# lilypad_V2.net
KiCad netlist of a schematic drawn in EAGLE
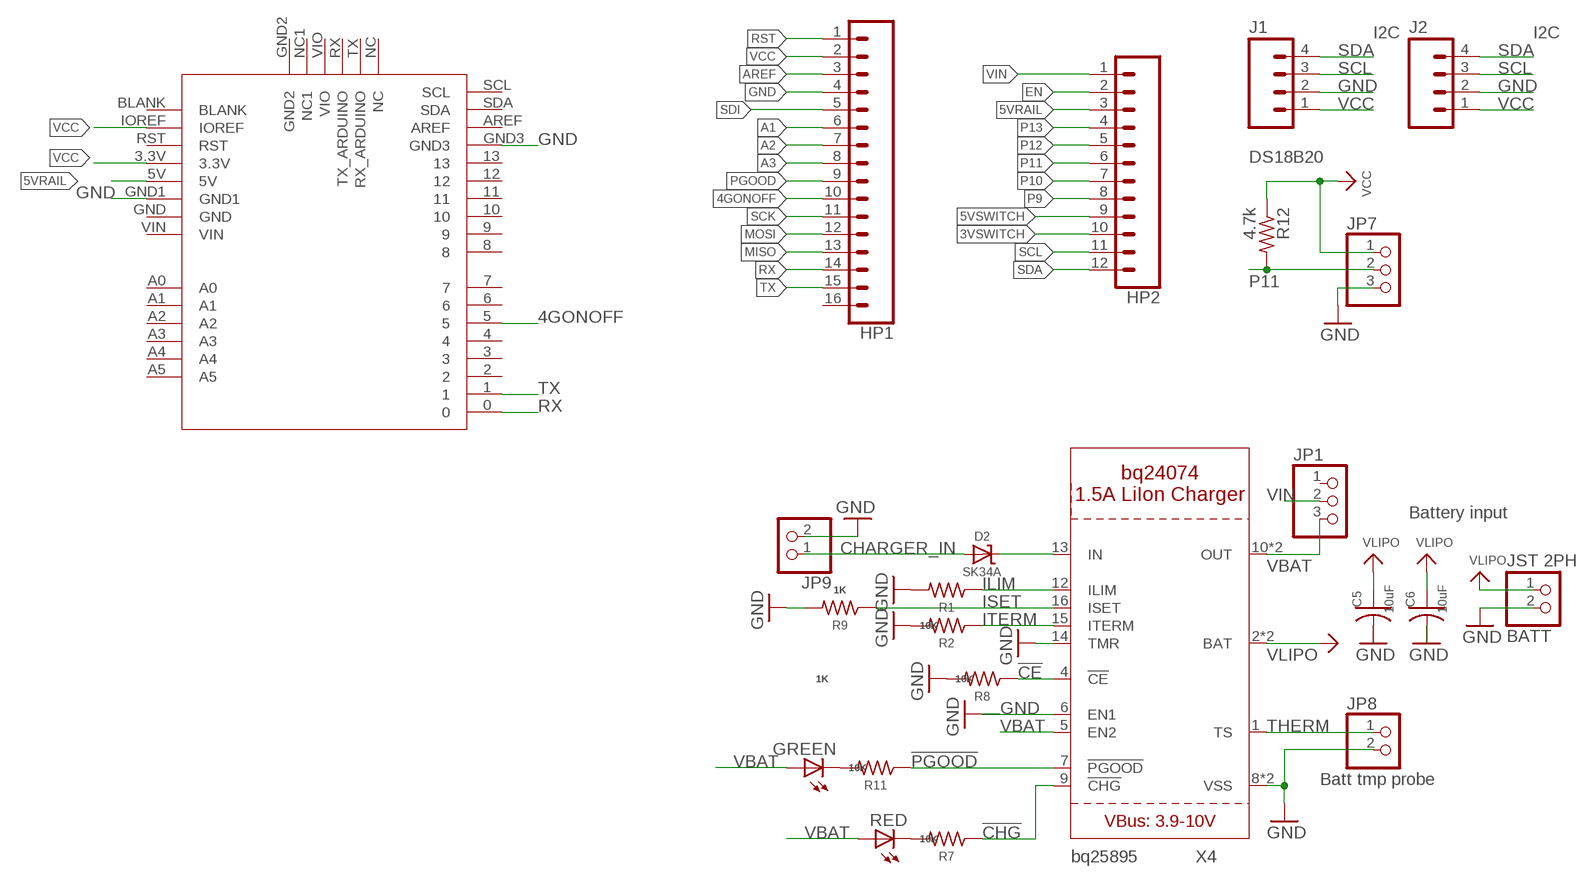
[diagram p0: schematic, sheet 1]

(export (version "E")
  (design (tool "Eeschema 10.0.6"))
  (components
    (comp (ref "BATT")
      (value "JST 2PH")
      (footprint "eagle-import:JST-PH-2-SMT-RA")
      (libsource (lib "eagle-import") (part "JST_2PIN-SMT-RA"))
    )
    (comp (ref "C5")
      (value "10uF")
      (footprint "eagle-import:C0805K")
      (libsource (lib "eagle-import") (part "C-USC0805K"))
    )
    (comp (ref "C6")
      (value "10uF")
      (footprint "eagle-import:C0805K")
      (libsource (lib "eagle-import") (part "C-USC0805K"))
    )
    (comp (ref "D2")
      (value "SK34A")
      (footprint "eagle-import:SMADIODE")
      (libsource (lib "eagle-import") (part "DIODE-SCHOTTKYSMA"))
    )
    (comp (ref "GREEN")
      (value "LEDSMT1206")
      (footprint "eagle-import:1206")
      (libsource (lib "eagle-import") (part "LEDSMT1206"))
    )
    (comp (ref "HP1")
      (value "CONN_16")
      (footprint "eagle-import:1X16")
      (libsource (lib "eagle-import") (part "CONN_16"))
    )
    (comp (ref "HP2")
      (value "CONN_12")
      (footprint "eagle-import:1X12")
      (libsource (lib "eagle-import") (part "CONN_12"))
    )
    (comp (ref "J1")
      (value "M04PTH")
      (footprint "eagle-import:1X04")
      (libsource (lib "eagle-import") (part "M04PTH"))
    )
    (comp (ref "J2")
      (value "M04PTH")
      (footprint "eagle-import:1X04")
      (libsource (lib "eagle-import") (part "M04PTH"))
    )
    (comp (ref "JP1")
      (value "PINHD-1X3")
      (footprint "eagle-import:1X03")
      (libsource (lib "eagle-import") (part "PINHD-1X3"))
    )
    (comp (ref "JP7")
      (value "PINHD-1X3")
      (footprint "eagle-import:1X03")
      (libsource (lib "eagle-import") (part "PINHD-1X3"))
    )
    (comp (ref "JP8")
      (value "PINHD-1X2")
      (footprint "eagle-import:1X02")
      (libsource (lib "eagle-import") (part "PINHD-1X2"))
    )
    (comp (ref "JP9")
      (value "PINHD-1X2")
      (footprint "eagle-import:1X02")
      (libsource (lib "eagle-import") (part "PINHD-1X2"))
    )
    (comp (ref "R1")
      (value "1K")
      (footprint "eagle-import:M0805")
      (libsource (lib "eagle-import") (part "R-US_M0805"))
    )
    (comp (ref "R2")
      (value "10K")
      (footprint "eagle-import:M0805")
      (libsource (lib "eagle-import") (part "R-US_M0805"))
    )
    (comp (ref "R7")
      (value "10K")
      (footprint "eagle-import:M0805")
      (libsource (lib "eagle-import") (part "R-US_M0805"))
    )
    (comp (ref "R8")
      (value "10K")
      (footprint "eagle-import:M0805")
      (libsource (lib "eagle-import") (part "R-US_M0805"))
    )
    (comp (ref "R9")
      (value "1K")
      (footprint "eagle-import:M0805")
      (libsource (lib "eagle-import") (part "R-US_M0805"))
    )
    (comp (ref "R11")
      (value "10K")
      (footprint "eagle-import:M0805")
      (libsource (lib "eagle-import") (part "R-US_M0805"))
    )
    (comp (ref "R12")
      (value "4.7k")
      (footprint "eagle-import:0805-THM")
      (libsource (lib "eagle-import") (part "FLIPFLOP-RES"))
    )
    (comp (ref "RED")
      (value "LEDSMT1206")
      (footprint "eagle-import:1206")
      (libsource (lib "eagle-import") (part "LEDSMT1206"))
    )
    (comp (ref "U$2")
      (value "LTE_BOARD")
      (footprint "eagle-import:LTE_BOARD_FOOTPRINT")
      (libsource (lib "eagle-import") (part "LTE_BOARD"))
    )
    (comp (ref "X4")
      (value "BQ24074")
      (footprint "eagle-import:QFN16_3MM")
      (libsource (lib "eagle-import") (part "BQ24074"))
    )
  )
  (nets
    (net (code "1") (name "/CHARGER_IN") (class "Default")
      (node (ref "D2") (pin "A") (pinfunction "A_A") (pintype "passive"))
      (node (ref "JP9") (pin "1") (pinfunction "1_1") (pintype "passive"))
    )
    (net (code "2") (name "/ILIM") (class "Default")
      (node (ref "R1") (pin "1") (pinfunction "1_1") (pintype "passive"))
      (node (ref "X4") (pin "12") (pinfunction "ILIM_12") (pintype "input"))
    )
    (net (code "3") (name "/ISET") (class "Default")
      (node (ref "R9") (pin "1") (pinfunction "1_1") (pintype "passive"))
      (node (ref "X4") (pin "16") (pinfunction "ISET_16") (pintype "input"))
    )
    (net (code "4") (name "/ITERM") (class "Default")
      (node (ref "R2") (pin "1") (pinfunction "1_1") (pintype "passive"))
      (node (ref "X4") (pin "15") (pinfunction "ITERM_15") (pintype "input"))
    )
    (net (code "5") (name "/THERM") (class "Default")
      (node (ref "JP8") (pin "1") (pinfunction "1_1") (pintype "passive"))
      (node (ref "X4") (pin "1") (pinfunction "TS_1") (pintype "input"))
    )
    (net (code "6") (name "/VBAT") (class "Default")
      (node (ref "GREEN") (pin "A") (pinfunction "A_A") (pintype "passive"))
      (node (ref "JP1") (pin "3") (pinfunction "3_3") (pintype "passive"))
      (node (ref "RED") (pin "A") (pinfunction "A_A") (pintype "passive"))
      (node (ref "X4") (pin "10") (pinfunction "OUT_10") (pintype "output"))
      (node (ref "X4") (pin "11") (pinfunction "OUT_11") (pintype "output"))
      (node (ref "X4") (pin "5") (pinfunction "EN2_5") (pintype "input"))
    )
    (net (code "7") (name "/~{CE}") (class "Default")
      (node (ref "R8") (pin "1") (pinfunction "1_1") (pintype "passive"))
      (node (ref "X4") (pin "4") (pinfunction "~{CE}_4") (pintype "input"))
    )
    (net (code "8") (name "/~{CHG}") (class "Default")
      (node (ref "R7") (pin "1") (pinfunction "1_1") (pintype "passive"))
      (node (ref "X4") (pin "9") (pinfunction "~{CHG}_9") (pintype "output"))
    )
    (net (code "9") (name "/~{PGOOD}") (class "Default")
      (node (ref "R11") (pin "1") (pinfunction "1_1") (pintype "passive"))
      (node (ref "X4") (pin "7") (pinfunction "~{PGOOD}_7") (pintype "output"))
    )
    (net (code "10") (name "3VSWITCH") (class "Default")
      (node (ref "HP2") (pin "10") (pinfunction "10_10") (pintype "passive"))
    )
    (net (code "11") (name "4GONOFF") (class "Default")
      (node (ref "HP1") (pin "10") (pinfunction "10_10") (pintype "passive"))
      (node (ref "U$2") (pin "5") (pinfunction "5_5") (pintype "bidirectional"))
    )
    (net (code "12") (name "5VRAIL") (class "Default")
      (node (ref "HP2") (pin "3") (pinfunction "3_3") (pintype "passive"))
      (node (ref "U$2") (pin "5V") (pinfunction "5V_5V") (pintype "bidirectional"))
    )
    (net (code "13") (name "5VSWITCH") (class "Default")
      (node (ref "HP2") (pin "9") (pinfunction "9_9") (pintype "passive"))
    )
    (net (code "14") (name "A1") (class "Default")
      (node (ref "HP1") (pin "6") (pinfunction "6_6") (pintype "passive"))
    )
    (net (code "15") (name "A2") (class "Default")
      (node (ref "HP1") (pin "7") (pinfunction "7_7") (pintype "passive"))
    )
    (net (code "16") (name "A3") (class "Default")
      (node (ref "HP1") (pin "8") (pinfunction "8_8") (pintype "passive"))
    )
    (net (code "17") (name "AREF") (class "Default")
      (node (ref "HP1") (pin "3") (pinfunction "3_3") (pintype "passive"))
    )
    (net (code "18") (name "EN") (class "Default")
      (node (ref "HP2") (pin "2") (pinfunction "2_2") (pintype "passive"))
    )
    (net (code "19") (name "GND") (class "Default")
      (node (ref "BATT") (pin "2") (pinfunction "1_2") (pintype "passive"))
      (node (ref "C5") (pin "2") (pinfunction "2_2") (pintype "passive"))
      (node (ref "C6") (pin "2") (pinfunction "2_2") (pintype "passive"))
      (node (ref "HP1") (pin "4") (pinfunction "4_4") (pintype "passive"))
      (node (ref "J1") (pin "2") (pinfunction "2_2") (pintype "passive"))
      (node (ref "J2") (pin "2") (pinfunction "2_2") (pintype "passive"))
      (node (ref "JP7") (pin "3") (pinfunction "3_3") (pintype "passive"))
      (node (ref "JP8") (pin "2") (pinfunction "2_2") (pintype "passive"))
      (node (ref "JP9") (pin "2") (pinfunction "2_2") (pintype "passive"))
      (node (ref "R1") (pin "2") (pinfunction "2_2") (pintype "passive"))
      (node (ref "R2") (pin "2") (pinfunction "2_2") (pintype "passive"))
      (node (ref "R8") (pin "2") (pinfunction "2_2") (pintype "passive"))
      (node (ref "R9") (pin "2") (pinfunction "2_2") (pintype "passive"))
      (node (ref "U$2") (pin "GND1") (pinfunction "GND1_GND1") (pintype "bidirectional"))
      (node (ref "U$2") (pin "GND3") (pinfunction "GND3_GND3") (pintype "bidirectional"))
      (node (ref "X4") (pin "14") (pinfunction "TMR_14") (pintype "input"))
      (node (ref "X4") (pin "6") (pinfunction "EN1_6") (pintype "input"))
      (node (ref "X4") (pin "8") (pinfunction "VSS_8") (pintype "power_in"))
      (node (ref "X4") (pin "THERMAL") (pinfunction "VSS_THERMAL") (pintype "power_in"))
    )
    (net (code "20") (name "MISO") (class "Default")
      (node (ref "HP1") (pin "13") (pinfunction "13_13") (pintype "passive"))
    )
    (net (code "21") (name "MOSI") (class "Default")
      (node (ref "HP1") (pin "12") (pinfunction "12_12") (pintype "passive"))
    )
    (net (code "22") (name "Net-(GREEN-PadC)") (class "Default")
      (node (ref "GREEN") (pin "C") (pinfunction "C_C") (pintype "passive"))
      (node (ref "R11") (pin "2") (pinfunction "2_2") (pintype "passive"))
    )
    (net (code "23") (name "Net-(R7-Pad2)") (class "Default")
      (node (ref "R7") (pin "2") (pinfunction "2_2") (pintype "passive"))
      (node (ref "RED") (pin "C") (pinfunction "C_C") (pintype "passive"))
    )
    (net (code "24") (name "Net-(X4-IN)") (class "Default")
      (node (ref "D2") (pin "C") (pinfunction "C_C") (pintype "passive"))
      (node (ref "X4") (pin "13") (pinfunction "IN_13") (pintype "power_in"))
    )
    (net (code "25") (name "P9") (class "Default")
      (node (ref "HP2") (pin "8") (pinfunction "8_8") (pintype "passive"))
    )
    (net (code "26") (name "P10") (class "Default")
      (node (ref "HP2") (pin "7") (pinfunction "7_7") (pintype "passive"))
    )
    (net (code "27") (name "P11") (class "Default")
      (node (ref "HP2") (pin "6") (pinfunction "6_6") (pintype "passive"))
      (node (ref "JP7") (pin "2") (pinfunction "2_2") (pintype "passive"))
      (node (ref "R12") (pin "2") (pinfunction "2_2") (pintype "passive"))
    )
    (net (code "28") (name "P12") (class "Default")
      (node (ref "HP2") (pin "5") (pinfunction "5_5") (pintype "passive"))
    )
    (net (code "29") (name "P13") (class "Default")
      (node (ref "HP2") (pin "4") (pinfunction "4_4") (pintype "passive"))
    )
    (net (code "30") (name "PGOOD") (class "Default")
      (node (ref "HP1") (pin "9") (pinfunction "9_9") (pintype "passive"))
    )
    (net (code "31") (name "RST") (class "Default")
      (node (ref "HP1") (pin "1") (pinfunction "1_1") (pintype "passive"))
    )
    (net (code "32") (name "RX") (class "Default")
      (node (ref "HP1") (pin "14") (pinfunction "14_14") (pintype "passive"))
      (node (ref "U$2") (pin "0") (pinfunction "0_0") (pintype "bidirectional"))
    )
    (net (code "33") (name "SCK") (class "Default")
      (node (ref "HP1") (pin "11") (pinfunction "11_11") (pintype "passive"))
    )
    (net (code "34") (name "SCL") (class "Default")
      (node (ref "HP2") (pin "11") (pinfunction "11_11") (pintype "passive"))
      (node (ref "J1") (pin "3") (pinfunction "3_3") (pintype "passive"))
      (node (ref "J2") (pin "3") (pinfunction "3_3") (pintype "passive"))
    )
    (net (code "35") (name "SDA") (class "Default")
      (node (ref "HP2") (pin "12") (pinfunction "12_12") (pintype "passive"))
      (node (ref "J1") (pin "4") (pinfunction "4_4") (pintype "passive"))
      (node (ref "J2") (pin "4") (pinfunction "4_4") (pintype "passive"))
    )
    (net (code "36") (name "SDI") (class "Default")
      (node (ref "HP1") (pin "5") (pinfunction "5_5") (pintype "passive"))
    )
    (net (code "37") (name "TX") (class "Default")
      (node (ref "HP1") (pin "15") (pinfunction "15_15") (pintype "passive"))
      (node (ref "U$2") (pin "1") (pinfunction "1_1") (pintype "bidirectional"))
    )
    (net (code "38") (name "VCC") (class "Default")
      (node (ref "HP1") (pin "2") (pinfunction "2_2") (pintype "passive"))
      (node (ref "J1") (pin "1") (pinfunction "1_1") (pintype "passive"))
      (node (ref "J2") (pin "1") (pinfunction "1_1") (pintype "passive"))
      (node (ref "JP7") (pin "1") (pinfunction "1_1") (pintype "passive"))
      (node (ref "R12") (pin "1") (pinfunction "1_1") (pintype "passive"))
      (node (ref "U$2") (pin "3.3V") (pinfunction "3.3V_3.3V") (pintype "bidirectional"))
      (node (ref "U$2") (pin "IOREF") (pinfunction "IOREF_IOREF") (pintype "bidirectional"))
    )
    (net (code "39") (name "VIN") (class "Default")
      (node (ref "HP2") (pin "1") (pinfunction "1_1") (pintype "passive"))
      (node (ref "JP1") (pin "2") (pinfunction "2_2") (pintype "passive"))
    )
    (net (code "40") (name "VLIPO") (class "Default")
      (node (ref "BATT") (pin "1") (pinfunction "2_1") (pintype "passive"))
      (node (ref "C5") (pin "1") (pinfunction "1_1") (pintype "passive"))
      (node (ref "C6") (pin "1") (pinfunction "1_1") (pintype "passive"))
      (node (ref "X4") (pin "2") (pinfunction "BAT_2") (pintype "input"))
      (node (ref "X4") (pin "3") (pinfunction "BAT_3") (pintype "input"))
    )
    (net (code "41") (name "unconnected-(HP1-Pad16)") (class "Default")
      (node (ref "HP1") (pin "16") (pinfunction "16_16") (pintype "passive"))
    )
    (net (code "42") (name "unconnected-(JP1-Pad1)") (class "Default")
      (node (ref "JP1") (pin "1") (pinfunction "1_1") (pintype "passive"))
    )
    (net (code "43") (name "unconnected-(U$2-Pad2)") (class "Default")
      (node (ref "U$2") (pin "2") (pinfunction "2_2") (pintype "bidirectional"))
    )
    (net (code "44") (name "unconnected-(U$2-Pad3)") (class "Default")
      (node (ref "U$2") (pin "3") (pinfunction "3_3") (pintype "bidirectional"))
    )
    (net (code "45") (name "unconnected-(U$2-Pad4)") (class "Default")
      (node (ref "U$2") (pin "4") (pinfunction "4_4") (pintype "bidirectional"))
    )
    (net (code "46") (name "unconnected-(U$2-Pad6)") (class "Default")
      (node (ref "U$2") (pin "6") (pinfunction "6_6") (pintype "bidirectional"))
    )
    (net (code "47") (name "unconnected-(U$2-Pad7)") (class "Default")
      (node (ref "U$2") (pin "7") (pinfunction "7_7") (pintype "bidirectional"))
    )
    (net (code "48") (name "unconnected-(U$2-Pad8)") (class "Default")
      (node (ref "U$2") (pin "8") (pinfunction "8_8") (pintype "bidirectional"))
    )
    (net (code "49") (name "unconnected-(U$2-Pad9)") (class "Default")
      (node (ref "U$2") (pin "9") (pinfunction "9_9") (pintype "bidirectional"))
    )
    (net (code "50") (name "unconnected-(U$2-Pad10)") (class "Default")
      (node (ref "U$2") (pin "10") (pinfunction "10_10") (pintype "bidirectional"))
    )
    (net (code "51") (name "unconnected-(U$2-Pad11)") (class "Default")
      (node (ref "U$2") (pin "11") (pinfunction "11_11") (pintype "bidirectional"))
    )
    (net (code "52") (name "unconnected-(U$2-Pad12)") (class "Default")
      (node (ref "U$2") (pin "12") (pinfunction "12_12") (pintype "bidirectional"))
    )
    (net (code "53") (name "unconnected-(U$2-Pad13)") (class "Default")
      (node (ref "U$2") (pin "13") (pinfunction "13_13") (pintype "bidirectional"))
    )
    (net (code "54") (name "unconnected-(U$2-PadA0)") (class "Default")
      (node (ref "U$2") (pin "A0") (pinfunction "A0_A0") (pintype "bidirectional"))
    )
    (net (code "55") (name "unconnected-(U$2-PadA1)") (class "Default")
      (node (ref "U$2") (pin "A1") (pinfunction "A1_A1") (pintype "bidirectional"))
    )
    (net (code "56") (name "unconnected-(U$2-PadA2)") (class "Default")
      (node (ref "U$2") (pin "A2") (pinfunction "A2_A2") (pintype "bidirectional"))
    )
    (net (code "57") (name "unconnected-(U$2-PadA3)") (class "Default")
      (node (ref "U$2") (pin "A3") (pinfunction "A3_A3") (pintype "bidirectional"))
    )
    (net (code "58") (name "unconnected-(U$2-PadA4)") (class "Default")
      (node (ref "U$2") (pin "A4") (pinfunction "A4_A4") (pintype "bidirectional"))
    )
    (net (code "59") (name "unconnected-(U$2-PadA5)") (class "Default")
      (node (ref "U$2") (pin "A5") (pinfunction "A5_A5") (pintype "bidirectional"))
    )
    (net (code "60") (name "unconnected-(U$2-PadAREF)") (class "Default")
      (node (ref "U$2") (pin "AREF") (pinfunction "AREF_AREF") (pintype "bidirectional"))
    )
    (net (code "61") (name "unconnected-(U$2-PadBLANK)") (class "Default")
      (node (ref "U$2") (pin "BLANK") (pinfunction "BLANK_BLANK") (pintype "bidirectional"))
    )
    (net (code "62") (name "unconnected-(U$2-PadGND)") (class "Default")
      (node (ref "U$2") (pin "GND") (pinfunction "GND_GND") (pintype "bidirectional"))
    )
    (net (code "63") (name "unconnected-(U$2-PadGND2)") (class "Default")
      (node (ref "U$2") (pin "GND2") (pinfunction "GND2_GND2") (pintype "bidirectional"))
    )
    (net (code "64") (name "unconnected-(U$2-PadNC)") (class "Default")
      (node (ref "U$2") (pin "NC") (pinfunction "NC_NC") (pintype "bidirectional"))
    )
    (net (code "65") (name "unconnected-(U$2-PadNC1)") (class "Default")
      (node (ref "U$2") (pin "NC1") (pinfunction "NC1_NC1") (pintype "bidirectional"))
    )
    (net (code "66") (name "unconnected-(U$2-PadRST)") (class "Default")
      (node (ref "U$2") (pin "RST") (pinfunction "RST_RST") (pintype "bidirectional"))
    )
    (net (code "67") (name "unconnected-(U$2-PadSCL)") (class "Default")
      (node (ref "U$2") (pin "SCL") (pinfunction "SCL_SCL") (pintype "bidirectional"))
    )
    (net (code "68") (name "unconnected-(U$2-PadSDA)") (class "Default")
      (node (ref "U$2") (pin "SDA") (pinfunction "SDA_SDA") (pintype "bidirectional"))
    )
    (net (code "69") (name "unconnected-(U$2-PadVIN)") (class "Default")
      (node (ref "U$2") (pin "VIN") (pinfunction "VIN_VIN") (pintype "bidirectional"))
    )
    (net (code "70") (name "unconnected-(U$2-PadVIO)") (class "Default")
      (node (ref "U$2") (pin "VIO") (pinfunction "VIO_VIO") (pintype "bidirectional"))
    )
    (net (code "71") (name "unconnected-(U$2-RX_ARDUINO-PadTX)") (class "Default")
      (node (ref "U$2") (pin "TX") (pinfunction "RX_ARDUINO_TX") (pintype "bidirectional"))
    )
    (net (code "72") (name "unconnected-(U$2-TX_ARDUINO-PadRX)") (class "Default")
      (node (ref "U$2") (pin "RX") (pinfunction "TX_ARDUINO_RX") (pintype "bidirectional"))
    )
  )
)
